# VoltageConverter_v2_2.net
KiCad netlist of a schematic drawn in EasyEDA Pro
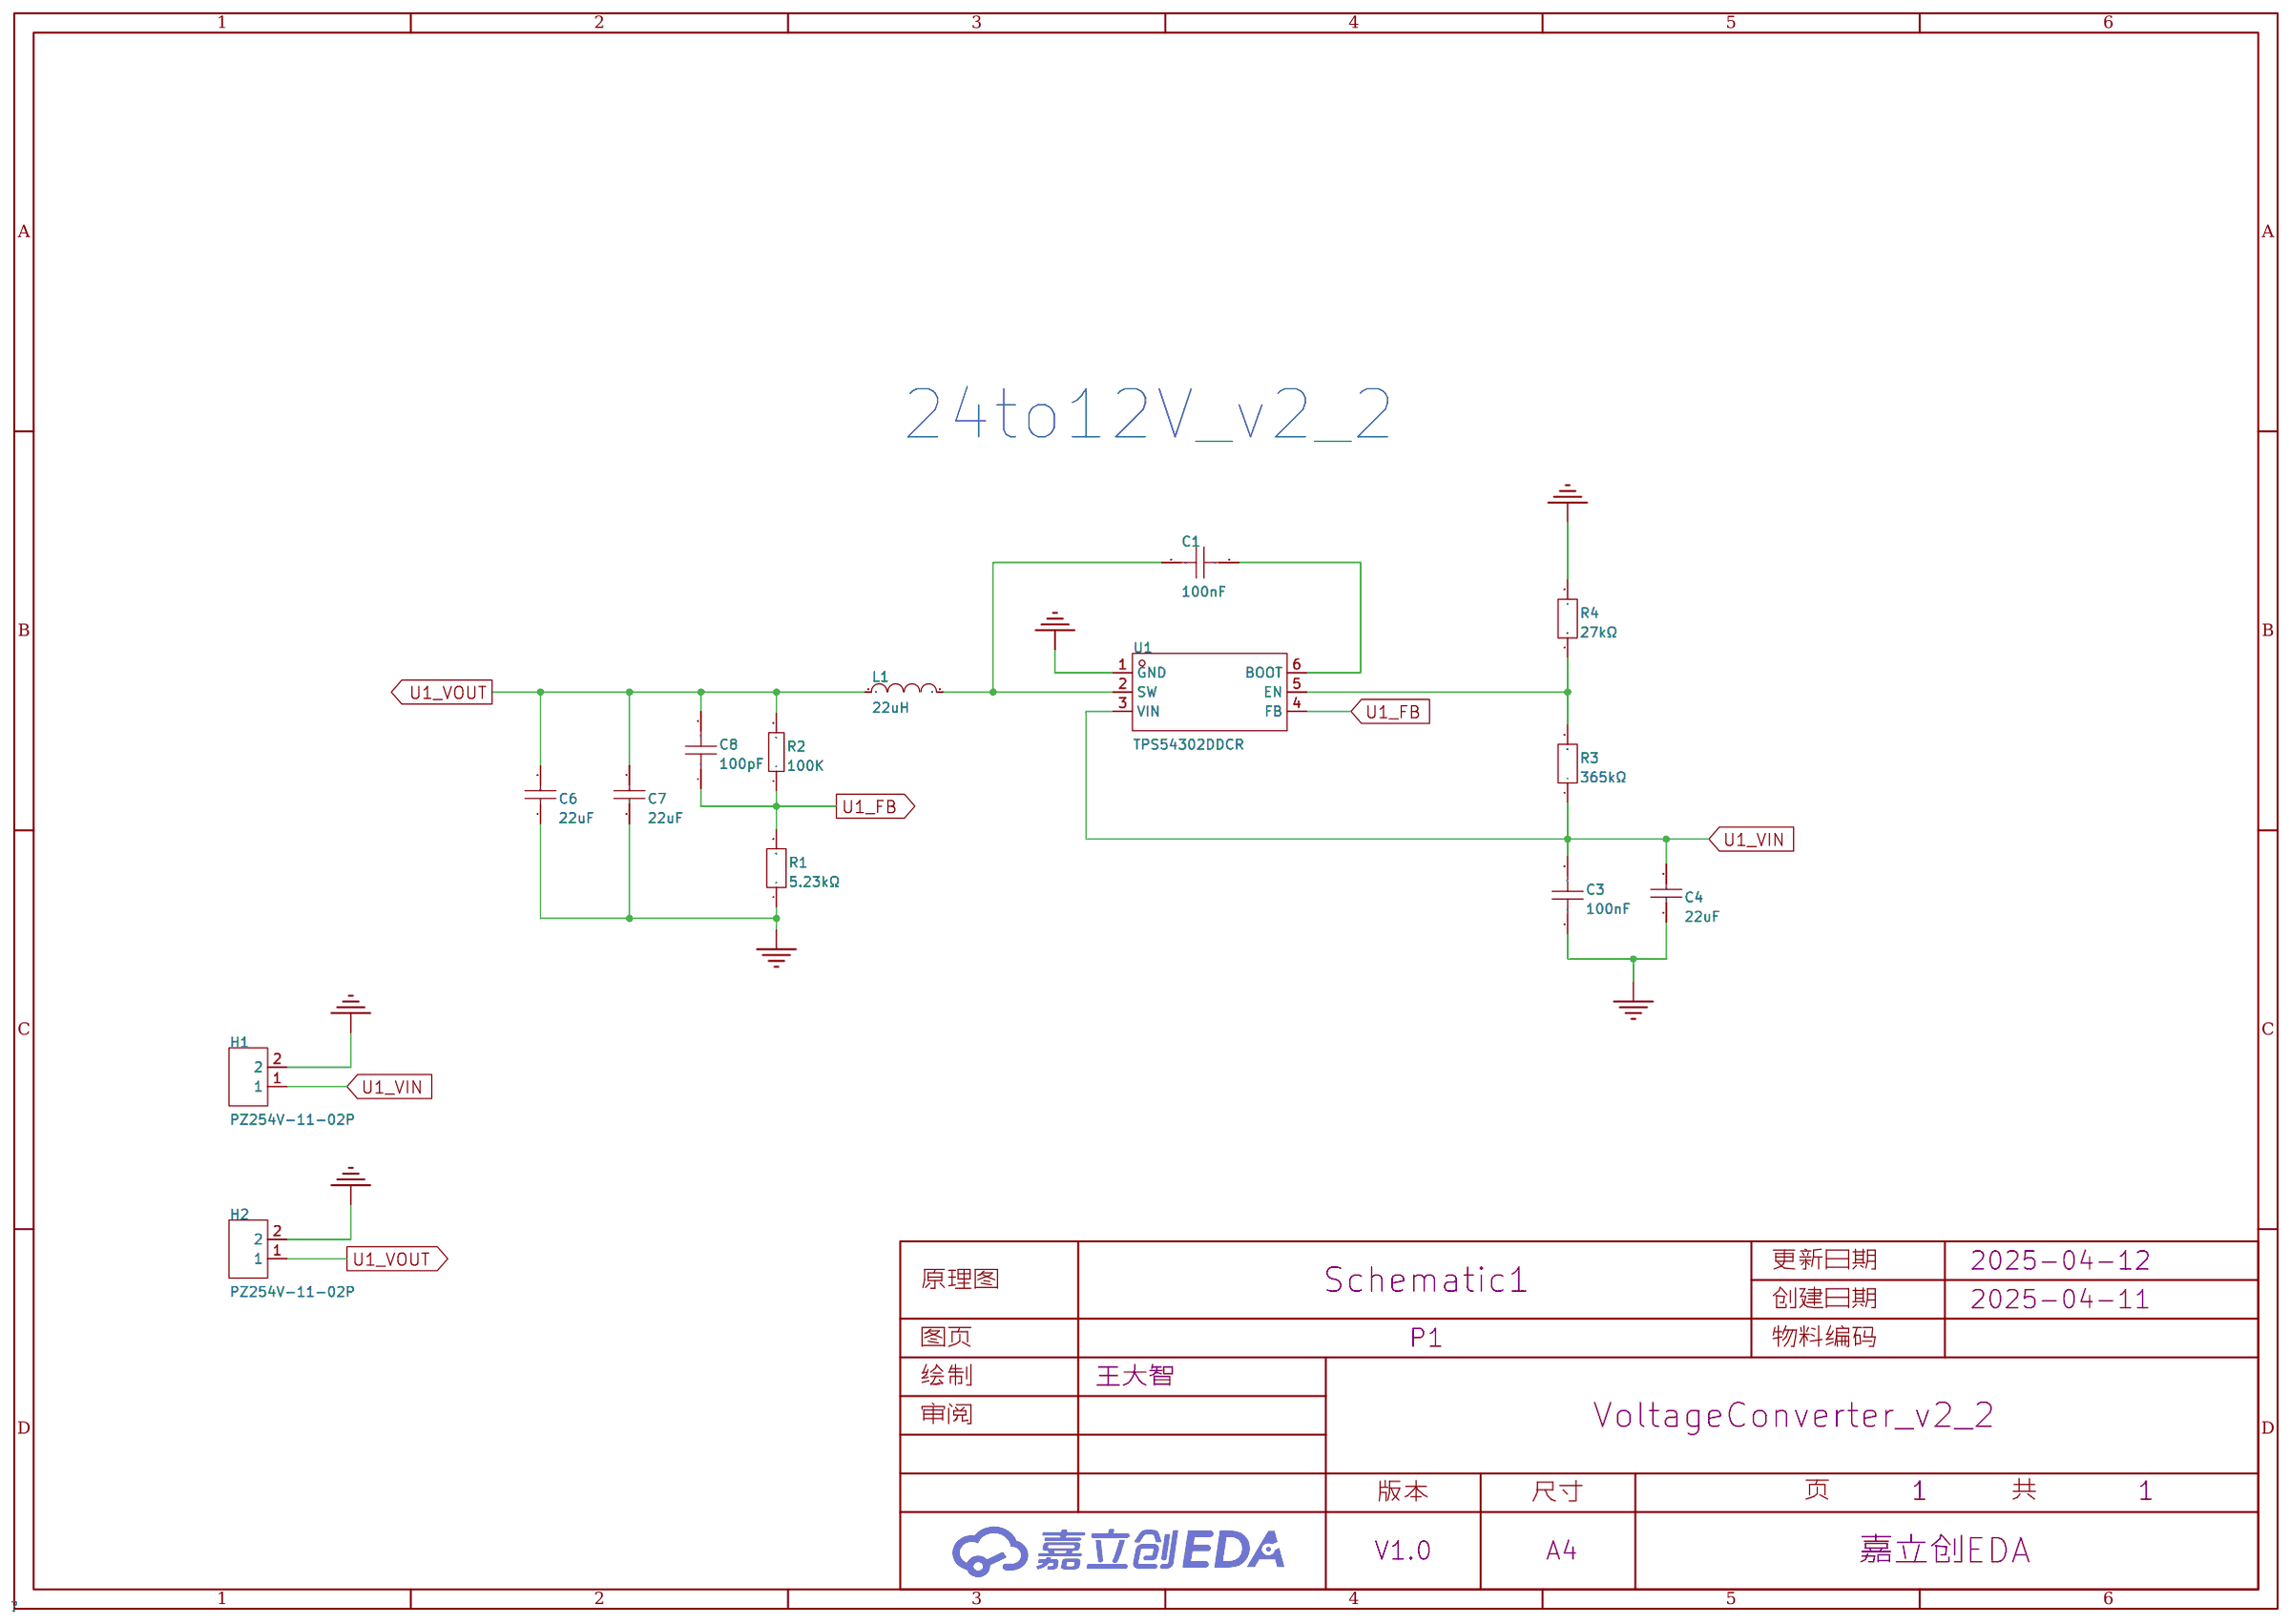
[diagram p0: schematic sheet]

(export (version "E")
  (design (tool "Eeschema 10.0.6"))
  (components
    (comp (ref "C1")
      (value "100nF")
      (footprint "easyedapro:C0603")
      (libsource (lib "easyedapro") (part "CapAcitance"))
    )
    (comp (ref "C3")
      (value "100nF")
      (footprint "easyedapro:C0603")
      (libsource (lib "easyedapro") (part "CapAcitance"))
    )
    (comp (ref "C4")
      (value "22uF")
      (footprint "easyedapro:C1206")
      (description "容值:22uF;精度:±10%;额定电压:25V;材质(温度系数):X5R;")
      (fields
        (field (name "Manufacturer Part") "CL31A226KAHNNNE")
        (field (name "Manufacturer") "SAMSUNG(三星)")
      )
      (libsource (lib "easyedapro") (part "CL31A226KAHNNNE"))
    )
    (comp (ref "C6")
      (value "22uF")
      (footprint "easyedapro:C1206")
      (description "容值:22uF;精度:±10%;额定电压:25V;材质(温度系数):X5R;")
      (fields
        (field (name "Manufacturer Part") "CL31A226KAHNNNE")
        (field (name "Manufacturer") "SAMSUNG(三星)")
      )
      (libsource (lib "easyedapro") (part "CL31A226KAHNNNE"))
    )
    (comp (ref "C7")
      (value "22uF")
      (footprint "easyedapro:C1206")
      (description "容值:22uF;精度:±10%;额定电压:25V;材质(温度系数):X5R;")
      (fields
        (field (name "Manufacturer Part") "CL31A226KAHNNNE")
        (field (name "Manufacturer") "SAMSUNG(三星)")
      )
      (libsource (lib "easyedapro") (part "CL31A226KAHNNNE"))
    )
    (comp (ref "C8")
      (value "100pF")
      (footprint "easyedapro:C0603")
      (description "容值:100pF;精度:±5%;额定电压:50V;材质(温度系数):NP0;")
      (fields
        (field (name "Manufacturer Part") "CC0603JRNPO9BN101")
        (field (name "Manufacturer") "YAGEO(国巨)")
      )
      (libsource (lib "easyedapro") (part "CC0603JRNPO9BN101"))
    )
    (comp (ref "H1")
      (value "PZ254V-11-02P")
      (footprint "easyedapro:HDR-TH_2P-P2.54-V-M")
      (fields (field (name "Manufacturer") "XFCN(兴飞)"))
      (libsource (lib "easyedapro") (part "PZ254V-11-02P"))
    )
    (comp (ref "H2")
      (value "PZ254V-11-02P")
      (footprint "easyedapro:HDR-TH_2P-P2.54-V-M")
      (fields (field (name "Manufacturer") "XFCN(兴飞)"))
      (libsource (lib "easyedapro") (part "PZ254V-11-02P"))
    )
    (comp (ref "L1")
      (value "22uH")
      (footprint "easyedapro:IND-SMD_L7.0-W6.6_FXL0630")
      (description "电感值:22uH;精度:±20%;额定电流:2.5A;饱和电流(Isat):3A;类型:一体成型电感;")
      (fields (field (name "Manufacturer Part") "FXL0630-220-M") (field (name "Manufacturer") "cjiang(长江微电)"))
      (libsource (lib "easyedapro") (part "FXL0630-220-M"))
    )
    (comp (ref "R1")
      (value "5.23kΩ")
      (footprint "easyedapro:R0805")
      (description "电阻类型:厚膜电阻;阻值:5.23kΩ;精度:±1%;功率:125mW;工作电压:150V;温度系数:±100ppm/°C;")
      (fields (field (name "Manufacturer Part") "FRC0805F5231TS") (field (name "Manufacturer") "FOJAN(富捷)"))
      (libsource (lib "easyedapro") (part "FRC0805F5231TS"))
    )
    (comp (ref "R2") (value "100K") (footprint "easyedapro:R0603") (libsource (lib "easyedapro") (part "电阻")))
    (comp (ref "R3")
      (value "365kΩ")
      (footprint "easyedapro:R1210")
      (description "电阻类型:厚膜电阻;阻值:365kΩ;精度:±1%;功率:500mW;最大工作电压:200V;温度系数:±100ppm/°C;")
      (fields (field (name "Manufacturer Part") "AC1210FR-07365KL") (field (name "Manufacturer") "YAGEO(国巨)"))
      (libsource (lib "easyedapro") (part "AC1210FR-07365KL"))
    )
    (comp (ref "R4")
      (value "27kΩ")
      (footprint "easyedapro:R0603")
      (description "电阻类型:厚膜电阻;阻值:27kΩ;精度:±1%;功率:100mW;工作电压:75V;温度系数:±100ppm/°C;")
      (fields (field (name "Manufacturer Part") "FRC0603F2702TS") (field (name "Manufacturer") "FOJAN(富捷)"))
      (libsource (lib "easyedapro") (part "FRC0603F2702TS"))
    )
    (comp (ref "U1")
      (value "TPS54302DDCR")
      (footprint "easyedapro:SOT-23-6_L2.9-W1.6-P0.95-LS2.8-BL")
      (description "功能类型:降压型;输出类型:固定;工作电压:4.5V~28V;输出电压:5V;输出电流:3A;")
      (fields (field (name "Manufacturer") "TI(德州仪器)"))
      (libsource (lib "easyedapro") (part "TPS54302DDCR_C311983"))
    )
  )
  (nets
    (net (code "1") (name "GND") (class "Default")
      (node (ref "C3") (pin "1") (pinfunction "1_1") (pintype "input"))
      (node (ref "C4") (pin "1") (pinfunction "1_1") (pintype "input"))
      (node (ref "C6") (pin "1") (pinfunction "1_1") (pintype "input"))
      (node (ref "C7") (pin "1") (pinfunction "1_1") (pintype "input"))
      (node (ref "H1") (pin "2") (pinfunction "2_2") (pintype "unspecified"))
      (node (ref "H2") (pin "2") (pinfunction "2_2") (pintype "unspecified"))
      (node (ref "R1") (pin "1") (pinfunction "1_1") (pintype "unspecified"))
      (node (ref "R4") (pin "2") (pinfunction "2_2") (pintype "unspecified"))
      (node (ref "U1") (pin "1") (pinfunction "GND_1") (pintype "unspecified"))
    )
    (net (code "2") (name "Net-(U1-BOOT)") (class "Default")
      (node (ref "C1") (pin "2") (pinfunction "2_2") (pintype "input"))
      (node (ref "U1") (pin "6") (pinfunction "BOOT_6") (pintype "unspecified"))
    )
    (net (code "3") (name "Net-(U1-EN)") (class "Default")
      (node (ref "R3") (pin "2") (pinfunction "2_2") (pintype "unspecified"))
      (node (ref "R4") (pin "1") (pinfunction "1_1") (pintype "unspecified"))
      (node (ref "U1") (pin "5") (pinfunction "EN_5") (pintype "unspecified"))
    )
    (net (code "4") (name "Net-(U1-SW)") (class "Default")
      (node (ref "C1") (pin "1") (pinfunction "1_1") (pintype "input"))
      (node (ref "L1") (pin "2") (pinfunction "2_2") (pintype "unspecified"))
      (node (ref "U1") (pin "2") (pinfunction "SW_2") (pintype "unspecified"))
    )
    (net (code "5") (name "U1_FB") (class "Default")
      (node (ref "C8") (pin "1") (pinfunction "1_1") (pintype "unspecified"))
      (node (ref "R1") (pin "2") (pinfunction "2_2") (pintype "unspecified"))
      (node (ref "R2") (pin "1") (pinfunction "1_1") (pintype "input"))
      (node (ref "U1") (pin "4") (pinfunction "FB_4") (pintype "unspecified"))
    )
    (net (code "6") (name "U1_VIN") (class "Default")
      (node (ref "C3") (pin "2") (pinfunction "2_2") (pintype "input"))
      (node (ref "C4") (pin "2") (pinfunction "2_2") (pintype "input"))
      (node (ref "H1") (pin "1") (pinfunction "1_1") (pintype "unspecified"))
      (node (ref "R3") (pin "1") (pinfunction "1_1") (pintype "unspecified"))
      (node (ref "U1") (pin "3") (pinfunction "VIN_3") (pintype "unspecified"))
    )
    (net (code "7") (name "U1_VOUT") (class "Default")
      (node (ref "C6") (pin "2") (pinfunction "2_2") (pintype "input"))
      (node (ref "C7") (pin "2") (pinfunction "2_2") (pintype "input"))
      (node (ref "C8") (pin "2") (pinfunction "2_2") (pintype "unspecified"))
      (node (ref "H2") (pin "1") (pinfunction "1_1") (pintype "unspecified"))
      (node (ref "L1") (pin "1") (pinfunction "1_1") (pintype "unspecified"))
      (node (ref "R2") (pin "2") (pinfunction "2_2") (pintype "input"))
    )
  )
)
